# FQDMDSchematic.net
KiCad netlist of a schematic drawn in Altium Designer
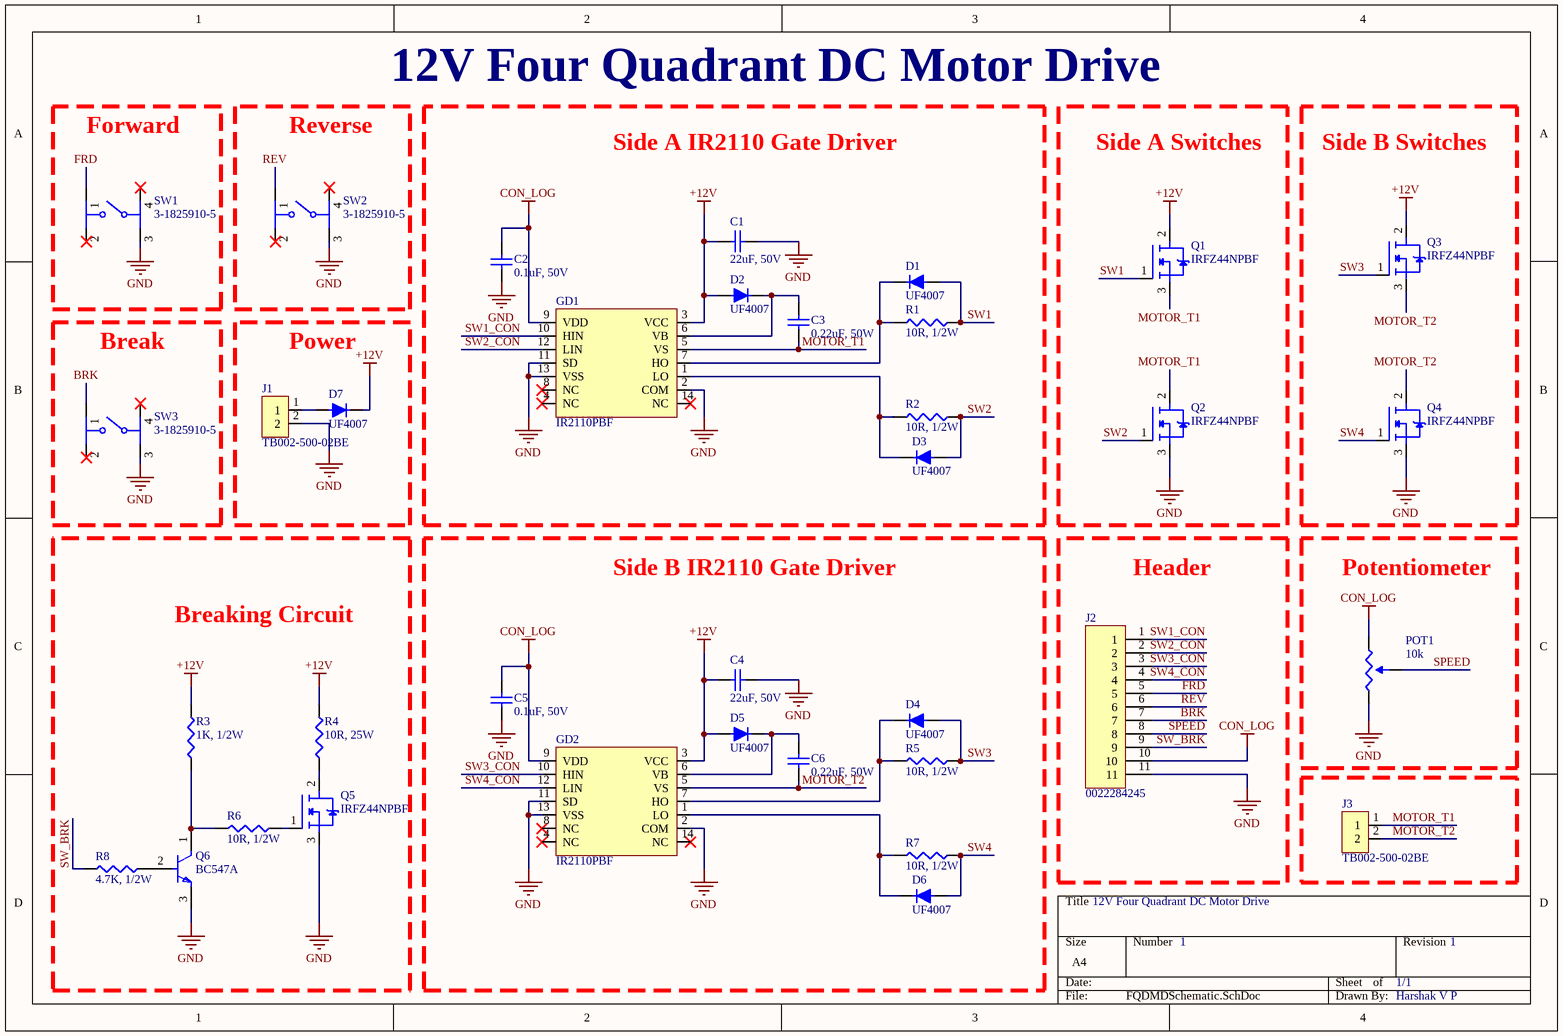
[diagram p0: FQDMDSchematic.SchDoc]

(export (version "E")
  (design (tool "Eeschema 10.0.6"))
  (components
    (comp (ref "C1")
      (value "22uF, 50V")
      (footprint "Capacitor_Polarized_TH")
      (description "CAP ALUM 22UF 20% 50V RADIAL TH")
      (fields
        (field (name "MANUFACTURER") "Yageo Group")
        (field (name "MANUFACTURER PART NUMBER") "SK226M050AC3AAKPLP")
      )
      (libsource (lib "FQDMDSchematicLibrary") (part "SK226M050AC3AAKPLP"))
    )
    (comp (ref "C2")
      (value "0.1uF, 50V")
      (footprint "Capacitor_Ceramic_TH")
      (description "CAP CER 0.1UF 50V X7R RADIAL")
      (fields
        (field (name "MANUFACTURER") "Yageo Group")
        (field (name "MANUFACTURER PART NUMBER") "C320C104K5R5TA")
      )
      (libsource (lib "FQDMDSchematicLibrary") (part "C320C104K5R5TA"))
    )
    (comp (ref "C3")
      (value "0.22uF, 50W")
      (footprint "Capacitor_Ceramic_TH")
      (description "CAP CER 0.22UF 50V Z5U RADIAL")
      (fields
        (field (name "MANUFACTURER") "Yageo Group")
        (field (name "MANUFACTURER PART NUMBER") "C322C224M5U5TA")
      )
      (libsource (lib "FQDMDSchematicLibrary") (part "C322C224M5U5TA"))
    )
    (comp (ref "C4")
      (value "22uF, 50V")
      (footprint "Capacitor_Polarized_TH")
      (description "CAP ALUM 22UF 20% 50V RADIAL TH")
      (fields
        (field (name "MANUFACTURER") "Yageo Group")
        (field (name "MANUFACTURER PART NUMBER") "SK226M050AC3AAKPLP")
      )
      (libsource (lib "FQDMDSchematicLibrary") (part "SK226M050AC3AAKPLP"))
    )
    (comp (ref "C5")
      (value "0.1uF, 50V")
      (footprint "Capacitor_Ceramic_TH")
      (description "CAP CER 0.1UF 50V X7R RADIAL")
      (fields
        (field (name "MANUFACTURER") "Yageo Group")
        (field (name "MANUFACTURER PART NUMBER") "C320C104K5R5TA")
      )
      (libsource (lib "FQDMDSchematicLibrary") (part "C320C104K5R5TA"))
    )
    (comp (ref "C6")
      (value "0.22uF, 50W")
      (footprint "Capacitor_Ceramic_TH")
      (description "CAP CER 0.22UF 50V Z5U RADIAL")
      (fields
        (field (name "MANUFACTURER") "Yageo Group")
        (field (name "MANUFACTURER PART NUMBER") "C322C224M5U5TA")
      )
      (libsource (lib "FQDMDSchematicLibrary") (part "C322C224M5U5TA"))
    )
    (comp (ref "D1")
      (value "UF4007")
      (footprint "Diode_TH")
      (description "DIODE STANDARD 1000V 1A DO204AC")
      (fields (field (name "MANUFACTURER") "Diotec"))
      (libsource (lib "FQDMDSchematicLibrary") (part "UF4007"))
    )
    (comp (ref "D2")
      (value "UF4007")
      (footprint "Diode_TH")
      (description "DIODE STANDARD 1000V 1A DO204AC")
      (fields (field (name "MANUFACTURER") "Diotec"))
      (libsource (lib "FQDMDSchematicLibrary") (part "UF4007"))
    )
    (comp (ref "D3")
      (value "UF4007")
      (footprint "Diode_TH")
      (description "DIODE STANDARD 1000V 1A DO204AC")
      (fields (field (name "MANUFACTURER") "Diotec"))
      (libsource (lib "FQDMDSchematicLibrary") (part "UF4007"))
    )
    (comp (ref "D4")
      (value "UF4007")
      (footprint "Diode_TH")
      (description "DIODE STANDARD 1000V 1A DO204AC")
      (fields (field (name "MANUFACTURER") "Diotec"))
      (libsource (lib "FQDMDSchematicLibrary") (part "UF4007"))
    )
    (comp (ref "D5")
      (value "UF4007")
      (footprint "Diode_TH")
      (description "DIODE STANDARD 1000V 1A DO204AC")
      (fields (field (name "MANUFACTURER") "Diotec"))
      (libsource (lib "FQDMDSchematicLibrary") (part "UF4007"))
    )
    (comp (ref "D6")
      (value "UF4007")
      (footprint "Diode_TH")
      (description "DIODE STANDARD 1000V 1A DO204AC")
      (fields (field (name "MANUFACTURER") "Diotec"))
      (libsource (lib "FQDMDSchematicLibrary") (part "UF4007"))
    )
    (comp (ref "D7")
      (value "UF4007")
      (footprint "Diode_TH")
      (description "DIODE STANDARD 1000V 1A DO204AC")
      (fields (field (name "MANUFACTURER") "Diotec"))
      (libsource (lib "FQDMDSchematicLibrary") (part "UF4007"))
    )
    (comp (ref "GD1")
      (value "IR2110PBF")
      (footprint "IR2110PBF_DIP14")
      (description "IC GATE DRVR HALF-BRIDGE 14DIP")
      (fields (field (name "MANUFACTURER") "Infineon"))
      (libsource (lib "FQDMDSchematicLibrary") (part "IR2110PBF"))
    )
    (comp (ref "GD2")
      (value "IR2110PBF")
      (footprint "IR2110PBF_DIP14")
      (description "IC GATE DRVR HALF-BRIDGE 14DIP")
      (fields (field (name "MANUFACTURER") "Infineon"))
      (libsource (lib "FQDMDSchematicLibrary") (part "IR2110PBF"))
    )
    (comp (ref "J1")
      (value "TB002-500-02BE")
      (footprint "Terminal_Block")
      (description "TERMINAL BLOCK, SCREW TYPE, 5.00")
      (fields (field (name "MANUFACTURER") "Same Sky"))
      (libsource (lib "FQDMDSchematicLibrary") (part "TB002-500-02BE"))
    )
    (comp (ref "J2")
      (value "0022284245")
      (footprint "Conneting_Jumpers")
      (description "CONN HEADER VERT 24POS 2.54MM")
      (fields (field (name "MANUFACTURER") "Molex") (field (name "MANUFACTURER PART NUMBER") "22-28-4245"))
      (libsource (lib "FQDMDSchematicLibrary") (part "0022284245"))
    )
    (comp (ref "J3")
      (value "TB002-500-02BE")
      (footprint "Terminal_Block")
      (description "TERMINAL BLOCK, SCREW TYPE, 5.00")
      (fields (field (name "MANUFACTURER") "Same Sky"))
      (libsource (lib "FQDMDSchematicLibrary") (part "TB002-500-02BE"))
    )
    (comp (ref "POT1")
      (value "10k")
      (footprint "Potentiometer")
      (description "POT 10K OHM 1/2W CARBON LOG")
      (fields
        (field (name "MANUFACTURER") "Same Sky")
        (field (name "MANUFACTURER PART NUMBER") "PTN24B-C1015DPA")
      )
      (libsource (lib "FQDMDSchematicLibrary") (part "PTN24B-C1015DPA"))
    )
    (comp (ref "Q1")
      (value "IRFZ44NPBF")
      (footprint "IRFZ44NPBF")
      (description "MOSFET N-CH 55V 49A TO220AB")
      (fields (field (name "MANUFACTURER") "Infineon"))
      (libsource (lib "FQDMDSchematicLibrary") (part "IRFZ44NPBF"))
    )
    (comp (ref "Q2")
      (value "IRFZ44NPBF")
      (footprint "IRFZ44NPBF")
      (description "MOSFET N-CH 55V 49A TO220AB")
      (fields (field (name "MANUFACTURER") "Infineon"))
      (libsource (lib "FQDMDSchematicLibrary") (part "IRFZ44NPBF"))
    )
    (comp (ref "Q3")
      (value "IRFZ44NPBF")
      (footprint "IRFZ44NPBF")
      (description "MOSFET N-CH 55V 49A TO220AB")
      (fields (field (name "MANUFACTURER") "Infineon"))
      (libsource (lib "FQDMDSchematicLibrary") (part "IRFZ44NPBF"))
    )
    (comp (ref "Q4")
      (value "IRFZ44NPBF")
      (footprint "IRFZ44NPBF")
      (description "MOSFET N-CH 55V 49A TO220AB")
      (fields (field (name "MANUFACTURER") "Infineon"))
      (libsource (lib "FQDMDSchematicLibrary") (part "IRFZ44NPBF"))
    )
    (comp (ref "Q5")
      (value "IRFZ44NPBF")
      (footprint "IRFZ44NPBF")
      (description "MOSFET N-CH 55V 49A TO220AB")
      (fields (field (name "MANUFACTURER") "Infineon"))
      (libsource (lib "FQDMDSchematicLibrary") (part "IRFZ44NPBF"))
    )
    (comp (ref "Q6")
      (value "BC547A")
      (footprint "TRANS_BC547A")
      (description "TRANS NPN 45V 0.1A TO-92")
      (fields (field (name "MANUFACTURER") "Diotec"))
      (libsource (lib "FQDMDSchematicLibrary") (part "BC547A"))
    )
    (comp (ref "R1")
      (value "10R, 1/2W")
      (footprint "Resistor_TH")
      (description "RES 10 OHM 5% 1/2W AXIAL")
      (fields
        (field (name "MANUFACTURER") "Yageo Group")
        (field (name "MANUFACTURER PART NUMBER") "CFR-50JB-52-10R")
      )
      (libsource (lib "FQDMDSchematicLibrary") (part "CFR-50JB-52-10R"))
    )
    (comp (ref "R2")
      (value "10R, 1/2W")
      (footprint "Resistor_TH")
      (description "RES 10 OHM 5% 1/2W AXIAL")
      (fields
        (field (name "MANUFACTURER") "Yageo Group")
        (field (name "MANUFACTURER PART NUMBER") "CFR-50JB-52-10R")
      )
      (libsource (lib "FQDMDSchematicLibrary") (part "CFR-50JB-52-10R"))
    )
    (comp (ref "R3")
      (value "1K, 1/2W")
      (footprint "Resistor_TH")
      (description "RES 1K OHM 5% 1/2W AXIAL")
      (fields
        (field (name "MANUFACTURER") "Yageo Group")
        (field (name "MANUFACTURER PART NUMBER") "CFR50SJT-52-1K")
      )
      (libsource (lib "FQDMDSchematicLibrary") (part "CFR50SJT-52-1K"))
    )
    (comp (ref "R4")
      (value "10R, 25W")
      (footprint "Braking_Resistor")
      (description "RES CHAS MNT 10 OHM 1% 25W")
      (fields
        (field (name "MANUFACTURER") "Stackpole Electronics")
        (field (name "MANUFACTURER PART NUMBER") "KAL25FB10R0")
      )
      (libsource (lib "FQDMDSchematicLibrary") (part "KAL25FB10R0"))
    )
    (comp (ref "R5")
      (value "10R, 1/2W")
      (footprint "Resistor_TH")
      (description "RES 10 OHM 5% 1/2W AXIAL")
      (fields
        (field (name "MANUFACTURER") "Yageo Group")
        (field (name "MANUFACTURER PART NUMBER") "CFR-50JB-52-10R")
      )
      (libsource (lib "FQDMDSchematicLibrary") (part "CFR-50JB-52-10R"))
    )
    (comp (ref "R6")
      (value "10R, 1/2W")
      (footprint "Resistor_TH")
      (description "RES 10 OHM 5% 1/2W AXIAL")
      (fields
        (field (name "MANUFACTURER") "Yageo Group")
        (field (name "MANUFACTURER PART NUMBER") "CFR-50JB-52-10R")
      )
      (libsource (lib "FQDMDSchematicLibrary") (part "CFR-50JB-52-10R"))
    )
    (comp (ref "R7")
      (value "10R, 1/2W")
      (footprint "Resistor_TH")
      (description "RES 10 OHM 5% 1/2W AXIAL")
      (fields
        (field (name "MANUFACTURER") "Yageo Group")
        (field (name "MANUFACTURER PART NUMBER") "CFR-50JB-52-10R")
      )
      (libsource (lib "FQDMDSchematicLibrary") (part "CFR-50JB-52-10R"))
    )
    (comp (ref "R8")
      (value "4.7K, 1/2W")
      (footprint "Resistor_TH")
      (description "RES 4.7K OHM 5% 1/2W AXIAL")
      (fields
        (field (name "MANUFACTURER") "Yageo Group")
        (field (name "MANUFACTURER PART NUMBER") "CFR-50JT-52-4K7")
      )
      (libsource (lib "FQDMDSchematicLibrary") (part "CFR-50JT-52-4K7"))
    )
    (comp (ref "SW1")
      (value "3-1825910-5")
      (footprint "Pushbutton")
      (description "SWITCH TACTILE SPST-NO 0.05A 24V")
      (fields (field (name "MANUFACTURER") "TE Connectivity"))
      (libsource (lib "FQDMDSchematicLibrary") (part "3-1825910-5"))
    )
    (comp (ref "SW2")
      (value "3-1825910-5")
      (footprint "Pushbutton")
      (description "SWITCH TACTILE SPST-NO 0.05A 24V")
      (fields (field (name "MANUFACTURER") "TE Connectivity"))
      (libsource (lib "FQDMDSchematicLibrary") (part "3-1825910-5"))
    )
    (comp (ref "SW3")
      (value "3-1825910-5")
      (footprint "Pushbutton")
      (description "SWITCH TACTILE SPST-NO 0.05A 24V")
      (fields (field (name "MANUFACTURER") "TE Connectivity"))
      (libsource (lib "FQDMDSchematicLibrary") (part "3-1825910-5"))
    )
  )
  (nets
    (net (code "1") (name "+12V") (class "Default")
      (node (ref "C1") (pin "1") (pinfunction "1_1") (pintype "passive"))
      (node (ref "C4") (pin "1") (pinfunction "1_1") (pintype "passive"))
      (node (ref "D2") (pin "1") (pinfunction "1_1") (pintype "passive"))
      (node (ref "D5") (pin "1") (pinfunction "1_1") (pintype "passive"))
      (node (ref "D7") (pin "2") (pinfunction "2_2") (pintype "passive"))
      (node (ref "GD1") (pin "3") (pinfunction "VCC_3") (pintype "passive"))
      (node (ref "GD2") (pin "3") (pinfunction "VCC_3") (pintype "passive"))
      (node (ref "Q1") (pin "2") (pinfunction "D_2") (pintype "passive"))
      (node (ref "Q3") (pin "2") (pinfunction "D_2") (pintype "passive"))
      (node (ref "R3") (pin "2") (pinfunction "2_2") (pintype "passive"))
      (node (ref "R4") (pin "2") (pinfunction "2_2") (pintype "passive"))
    )
    (net (code "2") (name "/BRK") (class "Default")
      (node (ref "J2") (pin "7") (pinfunction "7_7") (pintype "passive"))
      (node (ref "SW3") (pin "1") (pinfunction "1_1") (pintype "passive"))
    )
    (net (code "3") (name "/FRD") (class "Default")
      (node (ref "J2") (pin "5") (pinfunction "5_5") (pintype "passive"))
      (node (ref "SW1") (pin "1") (pinfunction "1_1") (pintype "passive"))
    )
    (net (code "4") (name "/MOTOR_T1") (class "Default")
      (node (ref "C3") (pin "1") (pinfunction "1_1") (pintype "passive"))
      (node (ref "GD1") (pin "5") (pinfunction "VS_5") (pintype "passive"))
      (node (ref "J3") (pin "1") (pinfunction "1_1") (pintype "passive"))
      (node (ref "Q1") (pin "3") (pinfunction "S_3") (pintype "passive"))
      (node (ref "Q2") (pin "2") (pinfunction "D_2") (pintype "passive"))
    )
    (net (code "5") (name "/MOTOR_T2") (class "Default")
      (node (ref "C6") (pin "1") (pinfunction "1_1") (pintype "passive"))
      (node (ref "GD2") (pin "5") (pinfunction "VS_5") (pintype "passive"))
      (node (ref "J3") (pin "2") (pinfunction "2_2") (pintype "passive"))
      (node (ref "Q3") (pin "3") (pinfunction "S_3") (pintype "passive"))
      (node (ref "Q4") (pin "2") (pinfunction "D_2") (pintype "passive"))
    )
    (net (code "6") (name "/REV") (class "Default")
      (node (ref "J2") (pin "6") (pinfunction "6_6") (pintype "passive"))
      (node (ref "SW2") (pin "1") (pinfunction "1_1") (pintype "passive"))
    )
    (net (code "7") (name "/SPEED") (class "Default")
      (node (ref "J2") (pin "8") (pinfunction "8_8") (pintype "passive"))
      (node (ref "POT1") (pin "3") (pinfunction "3_3") (pintype "passive"))
    )
    (net (code "8") (name "/SW1") (class "Default")
      (node (ref "D1") (pin "1") (pinfunction "1_1") (pintype "passive"))
      (node (ref "Q1") (pin "1") (pinfunction "G_1") (pintype "passive"))
      (node (ref "R1") (pin "1") (pinfunction "1_1") (pintype "passive"))
    )
    (net (code "9") (name "/SW1_CON") (class "Default")
      (node (ref "GD1") (pin "10") (pinfunction "HIN_10") (pintype "passive"))
      (node (ref "J2") (pin "1") (pinfunction "1_1") (pintype "passive"))
    )
    (net (code "10") (name "/SW2") (class "Default")
      (node (ref "D3") (pin "1") (pinfunction "1_1") (pintype "passive"))
      (node (ref "Q2") (pin "1") (pinfunction "G_1") (pintype "passive"))
      (node (ref "R2") (pin "1") (pinfunction "1_1") (pintype "passive"))
    )
    (net (code "11") (name "/SW2_CON") (class "Default")
      (node (ref "GD1") (pin "12") (pinfunction "LIN_12") (pintype "passive"))
      (node (ref "J2") (pin "2") (pinfunction "2_2") (pintype "passive"))
    )
    (net (code "12") (name "/SW3") (class "Default")
      (node (ref "D4") (pin "1") (pinfunction "1_1") (pintype "passive"))
      (node (ref "Q3") (pin "1") (pinfunction "G_1") (pintype "passive"))
      (node (ref "R5") (pin "1") (pinfunction "1_1") (pintype "passive"))
    )
    (net (code "13") (name "/SW3_CON") (class "Default")
      (node (ref "GD2") (pin "10") (pinfunction "HIN_10") (pintype "passive"))
      (node (ref "J2") (pin "3") (pinfunction "3_3") (pintype "passive"))
    )
    (net (code "14") (name "/SW4") (class "Default")
      (node (ref "D6") (pin "1") (pinfunction "1_1") (pintype "passive"))
      (node (ref "Q4") (pin "1") (pinfunction "G_1") (pintype "passive"))
      (node (ref "R7") (pin "1") (pinfunction "1_1") (pintype "passive"))
    )
    (net (code "15") (name "/SW4_CON") (class "Default")
      (node (ref "GD2") (pin "12") (pinfunction "LIN_12") (pintype "passive"))
      (node (ref "J2") (pin "4") (pinfunction "4_4") (pintype "passive"))
    )
    (net (code "16") (name "/SW_BRK") (class "Default")
      (node (ref "J2") (pin "9") (pinfunction "9_9") (pintype "passive"))
      (node (ref "R8") (pin "1") (pinfunction "1_1") (pintype "passive"))
    )
    (net (code "17") (name "CON_LOG") (class "Default")
      (node (ref "C2") (pin "2") (pinfunction "2_2") (pintype "passive"))
      (node (ref "C5") (pin "2") (pinfunction "2_2") (pintype "passive"))
      (node (ref "GD1") (pin "9") (pinfunction "VDD_9") (pintype "passive"))
      (node (ref "GD2") (pin "9") (pinfunction "VDD_9") (pintype "passive"))
      (node (ref "J2") (pin "10") (pinfunction "10_10") (pintype "passive"))
      (node (ref "POT1") (pin "1") (pinfunction "1_1") (pintype "passive"))
    )
    (net (code "18") (name "GND") (class "Default")
      (node (ref "C1") (pin "2") (pinfunction "2_2") (pintype "passive"))
      (node (ref "C2") (pin "1") (pinfunction "1_1") (pintype "passive"))
      (node (ref "C4") (pin "2") (pinfunction "2_2") (pintype "passive"))
      (node (ref "C5") (pin "1") (pinfunction "1_1") (pintype "passive"))
      (node (ref "GD1") (pin "11") (pinfunction "SD_11") (pintype "passive"))
      (node (ref "GD1") (pin "13") (pinfunction "VSS_13") (pintype "passive"))
      (node (ref "GD1") (pin "2") (pinfunction "COM_2") (pintype "passive"))
      (node (ref "GD2") (pin "11") (pinfunction "SD_11") (pintype "passive"))
      (node (ref "GD2") (pin "13") (pinfunction "VSS_13") (pintype "passive"))
      (node (ref "GD2") (pin "2") (pinfunction "COM_2") (pintype "passive"))
      (node (ref "J1") (pin "2") (pinfunction "2_2") (pintype "passive"))
      (node (ref "J2") (pin "11") (pinfunction "11_11") (pintype "passive"))
      (node (ref "POT1") (pin "2") (pinfunction "2_2") (pintype "passive"))
      (node (ref "Q2") (pin "3") (pinfunction "S_3") (pintype "passive"))
      (node (ref "Q4") (pin "3") (pinfunction "S_3") (pintype "passive"))
      (node (ref "Q5") (pin "3") (pinfunction "S_3") (pintype "passive"))
      (node (ref "Q6") (pin "3") (pinfunction "E_3") (pintype "passive"))
      (node (ref "SW1") (pin "4") (pinfunction "4_4") (pintype "passive"))
      (node (ref "SW2") (pin "4") (pinfunction "4_4") (pintype "passive"))
      (node (ref "SW3") (pin "4") (pinfunction "4_4") (pintype "passive"))
    )
    (net (code "19") (name "Net-(D7-Pad1)") (class "Default")
      (node (ref "D7") (pin "1") (pinfunction "1_1") (pintype "passive"))
      (node (ref "J1") (pin "1") (pinfunction "1_1") (pintype "passive"))
    )
    (net (code "20") (name "Net-(GD1-HO)") (class "Default")
      (node (ref "D1") (pin "2") (pinfunction "2_2") (pintype "passive"))
      (node (ref "GD1") (pin "7") (pinfunction "HO_7") (pintype "passive"))
      (node (ref "R1") (pin "2") (pinfunction "2_2") (pintype "passive"))
    )
    (net (code "21") (name "Net-(GD1-LO)") (class "Default")
      (node (ref "D3") (pin "2") (pinfunction "2_2") (pintype "passive"))
      (node (ref "GD1") (pin "1") (pinfunction "LO_1") (pintype "passive"))
      (node (ref "R2") (pin "2") (pinfunction "2_2") (pintype "passive"))
    )
    (net (code "22") (name "Net-(GD1-VB)") (class "Default")
      (node (ref "C3") (pin "2") (pinfunction "2_2") (pintype "passive"))
      (node (ref "D2") (pin "2") (pinfunction "2_2") (pintype "passive"))
      (node (ref "GD1") (pin "6") (pinfunction "VB_6") (pintype "passive"))
    )
    (net (code "23") (name "Net-(GD2-HO)") (class "Default")
      (node (ref "D4") (pin "2") (pinfunction "2_2") (pintype "passive"))
      (node (ref "GD2") (pin "7") (pinfunction "HO_7") (pintype "passive"))
      (node (ref "R5") (pin "2") (pinfunction "2_2") (pintype "passive"))
    )
    (net (code "24") (name "Net-(GD2-LO)") (class "Default")
      (node (ref "D6") (pin "2") (pinfunction "2_2") (pintype "passive"))
      (node (ref "GD2") (pin "1") (pinfunction "LO_1") (pintype "passive"))
      (node (ref "R7") (pin "2") (pinfunction "2_2") (pintype "passive"))
    )
    (net (code "25") (name "Net-(GD2-VB)") (class "Default")
      (node (ref "C6") (pin "2") (pinfunction "2_2") (pintype "passive"))
      (node (ref "D5") (pin "2") (pinfunction "2_2") (pintype "passive"))
      (node (ref "GD2") (pin "6") (pinfunction "VB_6") (pintype "passive"))
    )
    (net (code "26") (name "Net-(Q5-D)") (class "Default")
      (node (ref "Q5") (pin "2") (pinfunction "D_2") (pintype "passive"))
      (node (ref "R4") (pin "1") (pinfunction "1_1") (pintype "passive"))
    )
    (net (code "27") (name "Net-(Q5-G)") (class "Default")
      (node (ref "Q5") (pin "1") (pinfunction "G_1") (pintype "passive"))
      (node (ref "R6") (pin "2") (pinfunction "2_2") (pintype "passive"))
    )
    (net (code "28") (name "Net-(Q6-B)") (class "Default")
      (node (ref "Q6") (pin "2") (pinfunction "B_2") (pintype "passive"))
      (node (ref "R8") (pin "2") (pinfunction "2_2") (pintype "passive"))
    )
    (net (code "29") (name "Net-(Q6-C)") (class "Default")
      (node (ref "Q6") (pin "1") (pinfunction "C_1") (pintype "passive"))
      (node (ref "R3") (pin "1") (pinfunction "1_1") (pintype "passive"))
      (node (ref "R6") (pin "1") (pinfunction "1_1") (pintype "passive"))
    )
    (net (code "30") (name "unconnected-(GD1-NC-Pad4)") (class "Default")
      (node (ref "GD1") (pin "4") (pinfunction "NC_4") (pintype "passive+no_connect"))
    )
    (net (code "31") (name "unconnected-(GD1-NC-Pad8)") (class "Default")
      (node (ref "GD1") (pin "8") (pinfunction "NC_8") (pintype "passive+no_connect"))
    )
    (net (code "32") (name "unconnected-(GD1-NC-Pad14)") (class "Default")
      (node (ref "GD1") (pin "14") (pinfunction "NC_14") (pintype "passive+no_connect"))
    )
    (net (code "33") (name "unconnected-(GD2-NC-Pad4)") (class "Default")
      (node (ref "GD2") (pin "4") (pinfunction "NC_4") (pintype "passive+no_connect"))
    )
    (net (code "34") (name "unconnected-(GD2-NC-Pad8)") (class "Default")
      (node (ref "GD2") (pin "8") (pinfunction "NC_8") (pintype "passive+no_connect"))
    )
    (net (code "35") (name "unconnected-(GD2-NC-Pad14)") (class "Default")
      (node (ref "GD2") (pin "14") (pinfunction "NC_14") (pintype "passive+no_connect"))
    )
    (net (code "36") (name "unconnected-(SW1-Pad2)") (class "Default")
      (node (ref "SW1") (pin "2") (pinfunction "2_2") (pintype "passive+no_connect"))
    )
    (net (code "37") (name "unconnected-(SW1-Pad3)") (class "Default")
      (node (ref "SW1") (pin "3") (pinfunction "3_3") (pintype "passive+no_connect"))
    )
    (net (code "38") (name "unconnected-(SW2-Pad2)") (class "Default")
      (node (ref "SW2") (pin "2") (pinfunction "2_2") (pintype "passive+no_connect"))
    )
    (net (code "39") (name "unconnected-(SW2-Pad3)") (class "Default")
      (node (ref "SW2") (pin "3") (pinfunction "3_3") (pintype "passive+no_connect"))
    )
    (net (code "40") (name "unconnected-(SW3-Pad2)") (class "Default")
      (node (ref "SW3") (pin "2") (pinfunction "2_2") (pintype "passive+no_connect"))
    )
    (net (code "41") (name "unconnected-(SW3-Pad3)") (class "Default")
      (node (ref "SW3") (pin "3") (pinfunction "3_3") (pintype "passive+no_connect"))
    )
  )
)
